# nrf91.net
KiCad netlist of a schematic drawn in Altium Designer
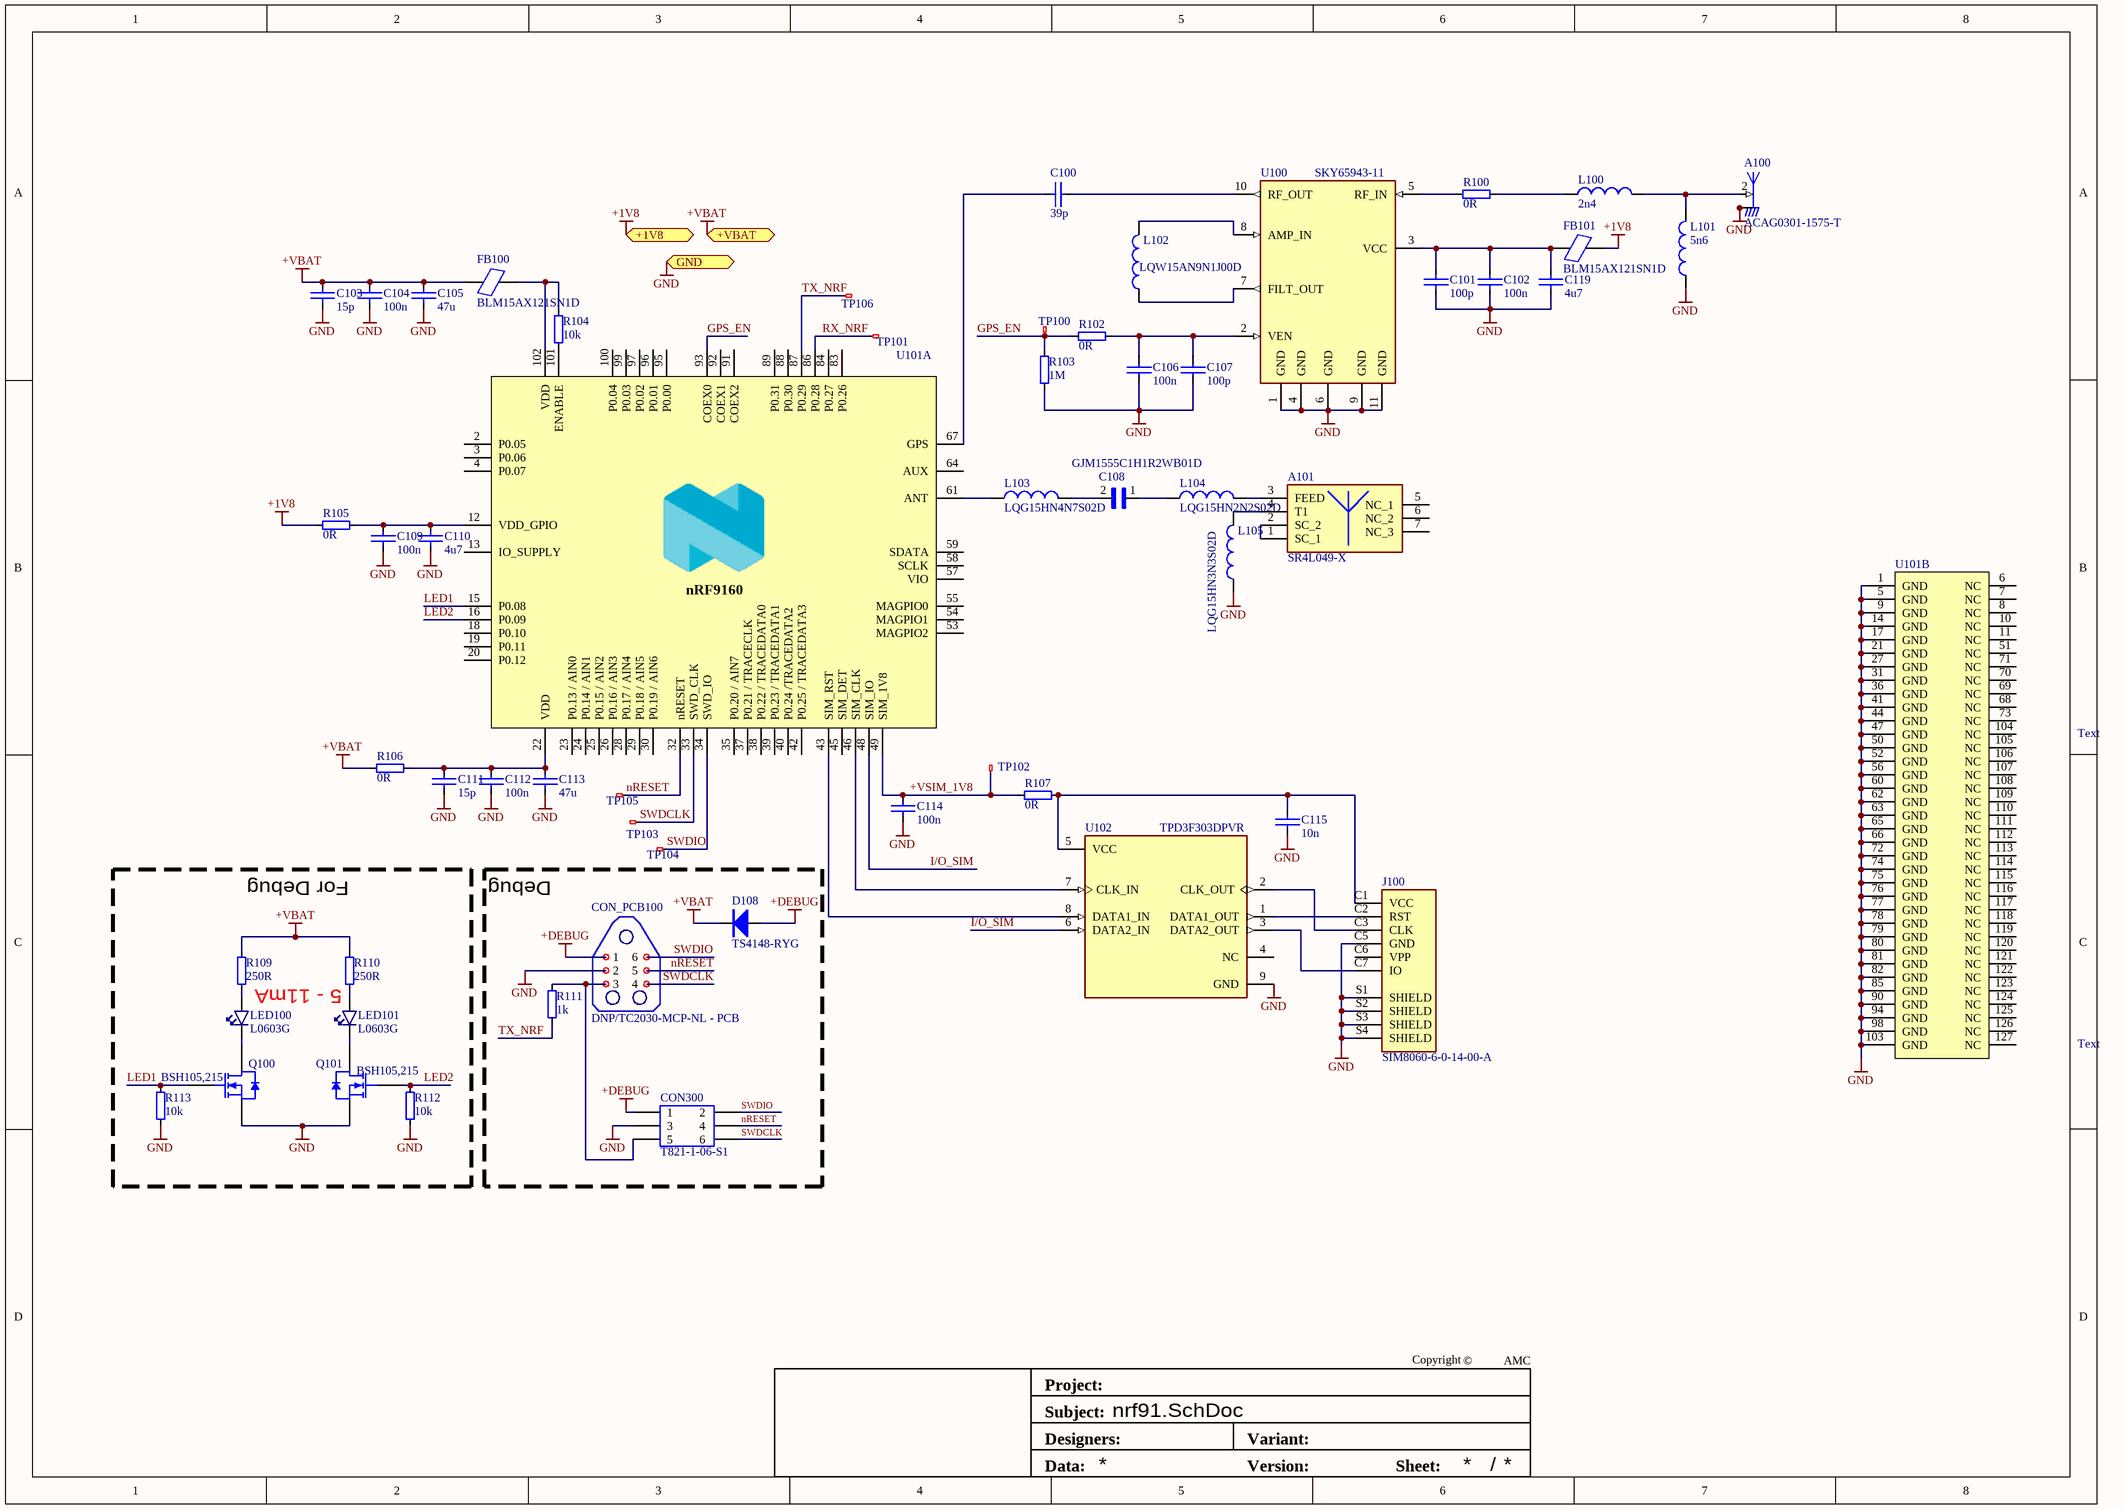
[diagram p0: nrf91.SchDoc]

(export (version "E")
  (design (tool "Eeschema 10.0.6"))
  (components
    (comp (ref "A100")
      (value "ACAG0301-1575-T")
      (footprint "ANT_ACAG0301-1575-T")
      (description "1.575GHz GPS Chip RF Antenna 1.565GHz ~ 1.585GHz 4.18dBi Solder Surface Mount")
      (fields (field (name "MF") "Abracon LLC"))
      (libsource (lib "GPS_LIB_SCH") (part "ACAG0301-1575-T"))
    )
    (comp (ref "A101")
      (value "SR4L049-X")
      (footprint "SR4L049R")
      (description "Antenna")
      (fields (field (name "MANUFACTURER_PART_NUMBER") "SR4L049-R"))
      (libsource (lib "GPS_LIB_SCH") (part "SR4L049-X"))
    )
    (comp (ref "C100")
      (value "39p")
      (footprint "0402_C")
      (description "Capacitor")
      (libsource (lib "ECS_AMC_all_2016") (part "CAP"))
    )
    (comp (ref "C101")
      (value "100p")
      (footprint "0402_C")
      (description "Capacitor")
      (libsource (lib "ECS_AMC_all_2016") (part "CAP"))
    )
    (comp (ref "C102")
      (value "100n")
      (footprint "0402_C")
      (description "Capacitor")
      (libsource (lib "ECS_AMC_all_2016") (part "CAP"))
    )
    (comp (ref "C103")
      (value "15p")
      (footprint "0402_C")
      (description "Capacitor")
      (libsource (lib "ECS_AMC_all_2016") (part "CAP"))
    )
    (comp (ref "C104")
      (value "100n")
      (footprint "0402_C")
      (description "Capacitor")
      (libsource (lib "ECS_AMC_all_2016") (part "CAP"))
    )
    (comp (ref "C105")
      (value "47u")
      (footprint "0805_c")
      (description "Capacitor")
      (libsource (lib "ECS_AMC_all_2016") (part "CAP"))
    )
    (comp (ref "C106")
      (value "100n")
      (footprint "0402_C")
      (description "Capacitor")
      (libsource (lib "ECS_AMC_all_2016") (part "CAP"))
    )
    (comp (ref "C107")
      (value "100p")
      (footprint "0402_C")
      (description "Capacitor")
      (libsource (lib "ECS_AMC_all_2016") (part "CAP"))
    )
    (comp (ref "C108")
      (value "GJM1555C1H1R2WB01D")
      (footprint "CAPC1005X55N")
      (libsource (lib "GPS_LIB_SCH") (part "GJM1555C1H1R2WB01D"))
    )
    (comp (ref "C109")
      (value "100n")
      (footprint "0402_C")
      (description "Capacitor")
      (libsource (lib "ECS_AMC_all_2016") (part "CAP"))
    )
    (comp (ref "C110")
      (value "4u7")
      (footprint "0603_C")
      (description "Capacitor")
      (libsource (lib "ECS_AMC_all_2016") (part "CAP"))
    )
    (comp (ref "C111")
      (value "15p")
      (footprint "0402_C")
      (description "Capacitor")
      (libsource (lib "ECS_AMC_all_2016") (part "CAP"))
    )
    (comp (ref "C112")
      (value "100n")
      (footprint "0402_C")
      (description "Capacitor")
      (libsource (lib "ECS_AMC_all_2016") (part "CAP"))
    )
    (comp (ref "C113")
      (value "47u")
      (footprint "0805_c")
      (description "Capacitor")
      (libsource (lib "ECS_AMC_all_2016") (part "CAP"))
    )
    (comp (ref "C114")
      (value "100n")
      (footprint "0402_C")
      (description "Capacitor")
      (libsource (lib "ECS_AMC_all_2016") (part "CAP"))
    )
    (comp (ref "C115")
      (value "10n")
      (footprint "0402_C")
      (description "Capacitor")
      (libsource (lib "ECS_AMC_all_2016") (part "CAP"))
    )
    (comp (ref "C119")
      (value "4u7")
      (footprint "0603_C")
      (description "Capacitor")
      (libsource (lib "ECS_AMC_all_2016") (part "CAP"))
    )
    (comp (ref "CON300")
      (value "T821-1-06-S1")
      (footprint "IDC_2X3_2.54MM")
      (libsource (lib "ECS_AMC_all_2016") (part "piny_2x3"))
    )
    (comp (ref "CON_PCB100")
      (value "DNP/TC2030-MCP-NL - PCB")
      (footprint "TC2030-MCP-NL - PCB")
      (libsource (lib "ECS_AMC_all_2016") (part "TC2030-MCP-NL - PCB"))
    )
    (comp (ref "D108")
      (value "TS4148-RYG")
      (footprint "0805D")
      (description "Diode")
      (libsource (lib "*") (part "DIODE"))
    )
    (comp (ref "FB100")
      (value "BLM15AX121SN1D")
      (footprint "0402_L")
      (description "Ferrite Bead")
      (libsource (lib "ECS_AMC_all_2016") (part "Ferrite_Bead"))
    )
    (comp (ref "FB101")
      (value "BLM15AX121SN1D")
      (footprint "0402_L")
      (description "Ferrite Bead")
      (libsource (lib "ECS_AMC_all_2016") (part "Ferrite_Bead"))
    )
    (comp (ref "J100")
      (value "SIM8060-6-0-14-00-A")
      (footprint "GCT_SIM8060-6-0-14-00-A")
      (description "6 Position Card Connector NANO SIM Surface Mount, Right Angle Gold")
      (fields (field (name "MF") "Global Connector Technology"))
      (libsource (lib "GPS_LIB_SCH") (part "SIM8060-6-0-14-00-A"))
    )
    (comp (ref "L100")
      (value "2n4")
      (footprint "0402")
      (description "inductor")
      (libsource (lib "ECS_AMC_all_2016") (part "Inductor"))
    )
    (comp (ref "L101")
      (value "5n6")
      (footprint "0402")
      (description "inductor")
      (libsource (lib "ECS_AMC_all_2016") (part "Inductor"))
    )
    (comp (ref "L102")
      (value "LQW15AN9N1J00D")
      (footprint "INDC1006X60N")
      (description "Inductor with Inductance: 9.1nH Tol. +/-5%, Package: 0402 (1005)")
      (fields (field (name "MF") "Murata"))
      (libsource (lib "GPS_LIB_SCH") (part "LQW15AN9N1J00D"))
    )
    (comp (ref "L103")
      (value "LQG15HN4N7S02D")
      (footprint "INDC1005X55N")
      (description "Ind RF Chip Multi-Layer 2.2nH 0.3nH 100MHz 8Q-Factor Air 300mA 0402 Paper T/R")
      (fields (field (name "MP") "LQG15HN2N2S02D"))
      (libsource (lib "GPS_LIB_SCH") (part "LQG15HN4N7S02D"))
    )
    (comp (ref "L104")
      (value "LQG15HN2N2S02D")
      (footprint "INDC1005X55N")
      (description "Ind RF Chip Multi-Layer 2.2nH 0.3nH 100MHz 8Q-Factor Air 300mA 0402 Paper T/R")
      (libsource (lib "GPS_LIB_SCH") (part "LQG15HN2N2S02D"))
    )
    (comp (ref "L105")
      (value "LQG15HN3N3S02D")
      (footprint "INDC1005X55N")
      (description "Ind RF Chip Multi-Layer 2.2nH 0.3nH 100MHz 8Q-Factor Air 300mA 0402 Paper T/R")
      (fields (field (name "MP") "LQG15HN2N2S02D"))
      (libsource (lib "GPS_LIB_SCH") (part "LQG15HN3N3S02D"))
    )
    (comp (ref "LED100")
      (value "L0603G")
      (footprint "LED_0603_G")
      (description "LED, Green, 0603, 573nm, Vf=2.0V, 24mcd, - 40 to +85°C")
      (fields
        (field (name "PART NUMBER") "VS 25C7M5")
        (field (name "MANUFACTURER") "Victory Electronics")
        (field (name "PUBLISHER") "Nordic Semiconductor")
      )
      (libsource (lib "ECS_AMC_all_2016") (part "D{colon}LED"))
    )
    (comp (ref "LED101")
      (value "L0603G")
      (footprint "LED_0603_G")
      (description "LED, Green, 0603, 573nm, Vf=2.0V, 24mcd, - 40 to +85°C")
      (fields
        (field (name "PART NUMBER") "VS 25C7M5")
        (field (name "MANUFACTURER") "Victory Electronics")
        (field (name "PUBLISHER") "Nordic Semiconductor")
      )
      (libsource (lib "ECS_AMC_all_2016") (part "D{colon}LED"))
    )
    (comp (ref "Q100")
      (value "BSH105,215")
      (footprint "SOT23-3D")
      (description "MOSFET N-CH, 170V, 6Ohm, 170mA, Single")
      (libsource (lib "ECS_AMC_all_2016") (part "BSS123_MN"))
    )
    (comp (ref "Q101")
      (value "BSH105,215")
      (footprint "SOT23-3D")
      (description "MOSFET N-CH, 170V, 6Ohm, 170mA, Single")
      (libsource (lib "ECS_AMC_all_2016") (part "BSS123_MN"))
    )
    (comp (ref "R100") (value "0R") (footprint "0402_r") (libsource (lib "ECS_AMC_all_2016") (part "RES")))
    (comp (ref "R102") (value "0R") (footprint "0603") (libsource (lib "ECS_AMC_all_2016") (part "RES")))
    (comp (ref "R103") (value "1M") (footprint "0603") (libsource (lib "") (part "RES_1")))
    (comp (ref "R104") (value "10k") (footprint "0603") (libsource (lib "") (part "RES_1")))
    (comp (ref "R105") (value "0R") (footprint "0603") (libsource (lib "ECS_AMC_all_2016") (part "RES")))
    (comp (ref "R106") (value "0R") (footprint "0603") (libsource (lib "ECS_AMC_all_2016") (part "RES")))
    (comp (ref "R107") (value "0R") (footprint "0603") (libsource (lib "") (part "RES_2")))
    (comp (ref "R109") (value "250R") (footprint "0603") (libsource (lib "ECS_AMC_all_2016") (part "RES")))
    (comp (ref "R110") (value "250R") (footprint "0603") (libsource (lib "ECS_AMC_all_2016") (part "RES")))
    (comp (ref "R111") (value "1k") (footprint "0603") (libsource (lib "") (part "RES_1")))
    (comp (ref "R112") (value "10k") (footprint "0603") (libsource (lib "ECS_AMC_all_2016") (part "RES")))
    (comp (ref "R113") (value "10k") (footprint "0603") (libsource (lib "ECS_AMC_all_2016") (part "RES")))
    (comp (ref "TP100")
      (value "testpointMini")
      (footprint "testpoint_50mils_round")
      (libsource (lib "ECS_AMC_all_2016") (part "testpointMini"))
    )
    (comp (ref "TP101")
      (value "testpointMini")
      (footprint "testpoint_50mils_round")
      (libsource (lib "ECS_AMC_all_2016") (part "testpointMini"))
    )
    (comp (ref "TP102")
      (value "testpointMini")
      (footprint "testpoint_50mils_round")
      (libsource (lib "ECS_AMC_all_2016") (part "testpointMini"))
    )
    (comp (ref "TP103")
      (value "testpointMini")
      (footprint "testpoint_50mils_round")
      (libsource (lib "ECS_AMC_all_2016") (part "testpointMini"))
    )
    (comp (ref "TP104")
      (value "testpointMini")
      (footprint "testpoint_50mils_round")
      (libsource (lib "ECS_AMC_all_2016") (part "testpointMini"))
    )
    (comp (ref "TP105")
      (value "testpointMini")
      (footprint "testpoint_50mils_round")
      (libsource (lib "ECS_AMC_all_2016") (part "testpointMini"))
    )
    (comp (ref "TP106")
      (value "testpointMini")
      (footprint "testpoint_50mils_round")
      (libsource (lib "ECS_AMC_all_2016") (part "testpointMini"))
    )
    (comp (ref "U100")
      (value "SKY65943-11")
      (footprint "IC_SKY65943-11")
      (description "RF Front End 1.559GHz ~ 1.606GHz Galileo, GLONASS, GNSS, GPS 10-MCM (2.5x2.5)")
      (fields (field (name "MF") "Skyworks Solutions Inc."))
      (libsource (lib "GPS_LIB_SCH") (part "SKY65943-11"))
    )
    (comp (ref "U101")
      (value "~")
      (footprint "nRF9160_SIP")
      (libsource (lib "GPS_LIB_SCH") (part "nRF9160_SIP"))
    )
    (comp (ref "U102")
      (value "TPD3F303DPVR")
      (footprint "SON50P210X160X65-9N")
      (libsource (lib "GPS_LIB_SCH") (part "TPD3F303DPVR"))
    )
  )
  (nets
    (net (code "1") (name "+1V8") (class "Default")
      (node (ref "FB101") (pin "2") (pinfunction "2_2") (pintype "passive"))
      (node (ref "R105") (pin "2") (pinfunction "2_2") (pintype "passive"))
    )
    (net (code "2") (name "+DEBUG") (class "Default")
      (node (ref "CON300") (pin "1") (pinfunction "1_1") (pintype "passive"))
      (node (ref "CON_PCB100") (pin "1") (pinfunction "1_1") (pintype "passive"))
      (node (ref "D108") (pin "2") (pinfunction "2_2") (pintype "passive"))
    )
    (net (code "3") (name "+VBAT") (class "Default")
      (node (ref "C103") (pin "2") (pinfunction "2_2") (pintype "passive"))
      (node (ref "C104") (pin "2") (pinfunction "2_2") (pintype "passive"))
      (node (ref "C105") (pin "2") (pinfunction "2_2") (pintype "passive"))
      (node (ref "D108") (pin "1") (pinfunction "1_1") (pintype "passive"))
      (node (ref "FB100") (pin "1") (pinfunction "1_1") (pintype "passive"))
      (node (ref "R106") (pin "2") (pinfunction "2_2") (pintype "passive"))
      (node (ref "R109") (pin "1") (pinfunction "1_1") (pintype "passive"))
      (node (ref "R110") (pin "1") (pinfunction "1_1") (pintype "passive"))
    )
    (net (code "4") (name "/+VSIM_1V8") (class "Default")
      (node (ref "C114") (pin "1") (pinfunction "1_1") (pintype "passive"))
      (node (ref "R107") (pin "1") (pinfunction "1_1") (pintype "passive"))
      (node (ref "TP102") (pin "1") (pinfunction "1_1") (pintype "passive"))
      (node (ref "U101") (pin "49") (pinfunction "SIM_1V8_49") (pintype "passive"))
    )
    (net (code "5") (name "/GPS_EN") (class "Default")
      (node (ref "R102") (pin "2") (pinfunction "2_2") (pintype "passive"))
      (node (ref "R103") (pin "2") (pinfunction "2_2") (pintype "passive"))
      (node (ref "TP100") (pin "1") (pinfunction "1_1") (pintype "passive"))
      (node (ref "U101") (pin "93") (pinfunction "COEX0_93") (pintype "passive"))
    )
    (net (code "6") (name "/I{slash}O_SIM") (class "Default")
      (node (ref "U101") (pin "48") (pinfunction "SIM_IO_48") (pintype "passive"))
      (node (ref "U102") (pin "6") (pinfunction "DATA2_IN_6") (pintype "input"))
    )
    (net (code "7") (name "/LED1") (class "Default")
      (node (ref "Q100") (pin "1") (pinfunction "G_1") (pintype "passive"))
      (node (ref "R113") (pin "1") (pinfunction "1_1") (pintype "passive"))
      (node (ref "U101") (pin "15") (pinfunction "P0.08_15") (pintype "passive"))
    )
    (net (code "8") (name "/LED2") (class "Default")
      (node (ref "Q101") (pin "1") (pinfunction "G_1") (pintype "passive"))
      (node (ref "R112") (pin "1") (pinfunction "1_1") (pintype "passive"))
      (node (ref "U101") (pin "16") (pinfunction "P0.09_16") (pintype "passive"))
    )
    (net (code "9") (name "/RX_NRF") (class "Default")
      (node (ref "TP101") (pin "1") (pinfunction "1_1") (pintype "passive"))
      (node (ref "U101") (pin "86") (pinfunction "P0.28_86") (pintype "passive"))
    )
    (net (code "10") (name "/SWDCLK") (class "Default")
      (node (ref "CON300") (pin "6") (pinfunction "6_6") (pintype "passive"))
      (node (ref "CON_PCB100") (pin "4") (pinfunction "4_4") (pintype "passive"))
      (node (ref "TP103") (pin "1") (pinfunction "1_1") (pintype "passive"))
      (node (ref "U101") (pin "33") (pinfunction "SWD_CLK_33") (pintype "passive"))
    )
    (net (code "11") (name "/SWDIO") (class "Default")
      (node (ref "CON300") (pin "2") (pinfunction "2_2") (pintype "passive"))
      (node (ref "CON_PCB100") (pin "6") (pinfunction "6_6") (pintype "passive"))
      (node (ref "TP104") (pin "1") (pinfunction "1_1") (pintype "passive"))
      (node (ref "U101") (pin "34") (pinfunction "SWD_IO_34") (pintype "passive"))
    )
    (net (code "12") (name "/TX_NRF") (class "Default")
      (node (ref "R111") (pin "1") (pinfunction "1_1") (pintype "passive"))
      (node (ref "TP106") (pin "1") (pinfunction "1_1") (pintype "passive"))
      (node (ref "U101") (pin "87") (pinfunction "P0.29_87") (pintype "passive"))
    )
    (net (code "13") (name "/nRESET") (class "Default")
      (node (ref "CON300") (pin "4") (pinfunction "4_4") (pintype "passive"))
      (node (ref "CON_PCB100") (pin "5") (pinfunction "5_5") (pintype "passive"))
      (node (ref "TP105") (pin "1") (pinfunction "1_1") (pintype "passive"))
      (node (ref "U101") (pin "32") (pinfunction "nRESET_32") (pintype "passive"))
    )
    (net (code "14") (name "GND") (class "Default")
      (node (ref "A100") (pin "1") (pinfunction "2_1") (pintype "passive"))
      (node (ref "A100") (pin "3") (pinfunction "2_3") (pintype "passive"))
      (node (ref "C101") (pin "1") (pinfunction "1_1") (pintype "passive"))
      (node (ref "C102") (pin "1") (pinfunction "1_1") (pintype "passive"))
      (node (ref "C103") (pin "1") (pinfunction "1_1") (pintype "passive"))
      (node (ref "C104") (pin "1") (pinfunction "1_1") (pintype "passive"))
      (node (ref "C105") (pin "1") (pinfunction "1_1") (pintype "passive"))
      (node (ref "C106") (pin "1") (pinfunction "1_1") (pintype "passive"))
      (node (ref "C107") (pin "1") (pinfunction "1_1") (pintype "passive"))
      (node (ref "C109") (pin "1") (pinfunction "1_1") (pintype "passive"))
      (node (ref "C110") (pin "1") (pinfunction "1_1") (pintype "passive"))
      (node (ref "C111") (pin "1") (pinfunction "1_1") (pintype "passive"))
      (node (ref "C112") (pin "1") (pinfunction "1_1") (pintype "passive"))
      (node (ref "C113") (pin "1") (pinfunction "1_1") (pintype "passive"))
      (node (ref "C114") (pin "2") (pinfunction "2_2") (pintype "passive"))
      (node (ref "C115") (pin "1") (pinfunction "1_1") (pintype "passive"))
      (node (ref "C119") (pin "1") (pinfunction "1_1") (pintype "passive"))
      (node (ref "CON300") (pin "3") (pinfunction "3_3") (pintype "passive"))
      (node (ref "CON_PCB100") (pin "2") (pinfunction "2_2") (pintype "passive"))
      (node (ref "J100") (pin "C5") (pinfunction "GND_C5") (pintype "passive"))
      (node (ref "J100") (pin "S1") (pinfunction "SHIELD_S1") (pintype "passive"))
      (node (ref "J100") (pin "S2") (pinfunction "SHIELD_S2") (pintype "passive"))
      (node (ref "J100") (pin "S3") (pinfunction "SHIELD_S3") (pintype "passive"))
      (node (ref "J100") (pin "S4") (pinfunction "SHIELD_S4") (pintype "passive"))
      (node (ref "L101") (pin "1") (pinfunction "1_1") (pintype "passive"))
      (node (ref "L105") (pin "1") (pinfunction "1_1") (pintype "passive"))
      (node (ref "Q100") (pin "2") (pinfunction "S_2") (pintype "passive"))
      (node (ref "Q101") (pin "2") (pinfunction "S_2") (pintype "passive"))
      (node (ref "R103") (pin "1") (pinfunction "1_1") (pintype "passive"))
      (node (ref "R112") (pin "2") (pinfunction "2_2") (pintype "passive"))
      (node (ref "R113") (pin "2") (pinfunction "2_2") (pintype "passive"))
      (node (ref "U100") (pin "1") (pinfunction "GND_1") (pintype "passive"))
      (node (ref "U100") (pin "11") (pinfunction "GND_11") (pintype "passive"))
      (node (ref "U100") (pin "4") (pinfunction "GND_4") (pintype "passive"))
      (node (ref "U100") (pin "6") (pinfunction "GND_6") (pintype "passive"))
      (node (ref "U100") (pin "9") (pinfunction "GND_9") (pintype "passive"))
      (node (ref "U101") (pin "1") (pinfunction "GND_1") (pintype "passive"))
      (node (ref "U101") (pin "103") (pinfunction "GND_103") (pintype "passive"))
      (node (ref "U101") (pin "14") (pinfunction "GND_14") (pintype "passive"))
      (node (ref "U101") (pin "17") (pinfunction "GND_17") (pintype "passive"))
      (node (ref "U101") (pin "21") (pinfunction "GND_21") (pintype "passive"))
      (node (ref "U101") (pin "27") (pinfunction "GND_27") (pintype "passive"))
      (node (ref "U101") (pin "31") (pinfunction "GND_31") (pintype "passive"))
      (node (ref "U101") (pin "36") (pinfunction "GND_36") (pintype "passive"))
      (node (ref "U101") (pin "41") (pinfunction "GND_41") (pintype "passive"))
      (node (ref "U101") (pin "44") (pinfunction "GND_44") (pintype "passive"))
      (node (ref "U101") (pin "47") (pinfunction "GND_47") (pintype "passive"))
      (node (ref "U101") (pin "5") (pinfunction "GND_5") (pintype "passive"))
      (node (ref "U101") (pin "50") (pinfunction "GND_50") (pintype "passive"))
      (node (ref "U101") (pin "52") (pinfunction "GND_52") (pintype "passive"))
      (node (ref "U101") (pin "56") (pinfunction "GND_56") (pintype "passive"))
      (node (ref "U101") (pin "60") (pinfunction "GND_60") (pintype "passive"))
      (node (ref "U101") (pin "62") (pinfunction "GND_62") (pintype "passive"))
      (node (ref "U101") (pin "63") (pinfunction "GND_63") (pintype "passive"))
      (node (ref "U101") (pin "65") (pinfunction "GND_65") (pintype "passive"))
      (node (ref "U101") (pin "66") (pinfunction "GND_66") (pintype "passive"))
      (node (ref "U101") (pin "72") (pinfunction "GND_72") (pintype "passive"))
      (node (ref "U101") (pin "74") (pinfunction "GND_74") (pintype "passive"))
      (node (ref "U101") (pin "75") (pinfunction "GND_75") (pintype "passive"))
      (node (ref "U101") (pin "76") (pinfunction "GND_76") (pintype "passive"))
      (node (ref "U101") (pin "77") (pinfunction "GND_77") (pintype "passive"))
      (node (ref "U101") (pin "78") (pinfunction "GND_78") (pintype "passive"))
      (node (ref "U101") (pin "79") (pinfunction "GND_79") (pintype "passive"))
      (node (ref "U101") (pin "80") (pinfunction "GND_80") (pintype "passive"))
      (node (ref "U101") (pin "81") (pinfunction "GND_81") (pintype "passive"))
      (node (ref "U101") (pin "82") (pinfunction "GND_82") (pintype "passive"))
      (node (ref "U101") (pin "85") (pinfunction "GND_85") (pintype "passive"))
      (node (ref "U101") (pin "9") (pinfunction "GND_9") (pintype "passive"))
      (node (ref "U101") (pin "90") (pinfunction "GND_90") (pintype "passive"))
      (node (ref "U101") (pin "94") (pinfunction "GND_94") (pintype "passive"))
      (node (ref "U101") (pin "98") (pinfunction "GND_98") (pintype "passive"))
      (node (ref "U102") (pin "9") (pinfunction "GND_9") (pintype "passive"))
    )
    (net (code "15") (name "Net-(A100-1)") (class "Default")
      (node (ref "A100") (pin "2") (pinfunction "1_2") (pintype "input"))
      (node (ref "L100") (pin "2") (pinfunction "2_2") (pintype "passive"))
      (node (ref "L101") (pin "2") (pinfunction "2_2") (pintype "passive"))
    )
    (net (code "16") (name "Net-(A101-FEED)") (class "Default")
      (node (ref "A101") (pin "3") (pinfunction "FEED_3") (pintype "passive"))
      (node (ref "L104") (pin "2") (pinfunction "2_2") (pintype "passive"))
    )
    (net (code "17") (name "Net-(A101-SC_1)") (class "Default")
      (node (ref "A101") (pin "1") (pinfunction "SC_1_1") (pintype "passive"))
      (node (ref "A101") (pin "2") (pinfunction "SC_2_2") (pintype "passive"))
    )
    (net (code "18") (name "Net-(A101-T1)") (class "Default")
      (node (ref "A101") (pin "4") (pinfunction "T1_4") (pintype "passive"))
      (node (ref "L105") (pin "2") (pinfunction "2_2") (pintype "passive"))
    )
    (net (code "19") (name "Net-(C108-Pad1)") (class "Default")
      (node (ref "C108") (pin "1") (pinfunction "1_1") (pintype "passive"))
      (node (ref "L104") (pin "1") (pinfunction "1_1") (pintype "passive"))
    )
    (net (code "20") (name "Net-(C108-Pad2)") (class "Default")
      (node (ref "C108") (pin "2") (pinfunction "2_2") (pintype "passive"))
      (node (ref "L103") (pin "2") (pinfunction "2_2") (pintype "passive"))
    )
    (net (code "21") (name "Net-(C111-Pad2)") (class "Default")
      (node (ref "C111") (pin "2") (pinfunction "2_2") (pintype "passive"))
      (node (ref "C112") (pin "2") (pinfunction "2_2") (pintype "passive"))
      (node (ref "C113") (pin "2") (pinfunction "2_2") (pintype "passive"))
      (node (ref "R106") (pin "1") (pinfunction "1_1") (pintype "passive"))
      (node (ref "U101") (pin "22") (pinfunction "VDD_22") (pintype "passive"))
    )
    (net (code "22") (name "Net-(CON300-Pad5)") (class "Default")
      (node (ref "CON300") (pin "5") (pinfunction "5_5") (pintype "passive"))
      (node (ref "CON_PCB100") (pin "3") (pinfunction "3_3") (pintype "passive"))
      (node (ref "R111") (pin "2") (pinfunction "2_2") (pintype "passive"))
    )
    (net (code "23") (name "Net-(FB100-Pad2)") (class "Default")
      (node (ref "FB100") (pin "2") (pinfunction "2_2") (pintype "passive"))
      (node (ref "R104") (pin "2") (pinfunction "2_2") (pintype "passive"))
      (node (ref "U101") (pin "102") (pinfunction "VDD_102") (pintype "passive"))
    )
    (net (code "24") (name "Net-(J100-CLK)") (class "Default")
      (node (ref "J100") (pin "C3") (pinfunction "CLK_C3") (pintype "passive"))
      (node (ref "U102") (pin "2") (pinfunction "CLK_OUT_2") (pintype "output"))
    )
    (net (code "25") (name "Net-(J100-IO)") (class "Default")
      (node (ref "J100") (pin "C7") (pinfunction "IO_C7") (pintype "passive"))
      (node (ref "U102") (pin "3") (pinfunction "DATA2_OUT_3") (pintype "output"))
    )
    (net (code "26") (name "Net-(J100-RST)") (class "Default")
      (node (ref "J100") (pin "C2") (pinfunction "RST_C2") (pintype "passive"))
      (node (ref "U102") (pin "1") (pinfunction "DATA1_OUT_1") (pintype "output"))
    )
    (net (code "27") (name "Net-(J100-VCC)") (class "Default")
      (node (ref "C115") (pin "2") (pinfunction "2_2") (pintype "passive"))
      (node (ref "J100") (pin "C1") (pinfunction "VCC_C1") (pintype "passive"))
      (node (ref "R107") (pin "2") (pinfunction "2_2") (pintype "passive"))
      (node (ref "U102") (pin "5") (pinfunction "VCC_5") (pintype "passive"))
    )
    (net (code "28") (name "Net-(L100-Pad1)") (class "Default")
      (node (ref "L100") (pin "1") (pinfunction "1_1") (pintype "passive"))
      (node (ref "R100") (pin "1") (pinfunction "1_1") (pintype "passive"))
    )
    (net (code "29") (name "Net-(LED100-A)") (class "Default")
      (node (ref "LED100") (pin "2") (pinfunction "A_2") (pintype "passive"))
      (node (ref "R109") (pin "2") (pinfunction "2_2") (pintype "passive"))
    )
    (net (code "30") (name "Net-(LED100-C)") (class "Default")
      (node (ref "LED100") (pin "1") (pinfunction "C_1") (pintype "passive"))
      (node (ref "Q100") (pin "3") (pinfunction "D_3") (pintype "passive"))
    )
    (net (code "31") (name "Net-(LED101-A)") (class "Default")
      (node (ref "LED101") (pin "2") (pinfunction "A_2") (pintype "passive"))
      (node (ref "R110") (pin "2") (pinfunction "2_2") (pintype "passive"))
    )
    (net (code "32") (name "Net-(LED101-C)") (class "Default")
      (node (ref "LED101") (pin "1") (pinfunction "C_1") (pintype "passive"))
      (node (ref "Q101") (pin "3") (pinfunction "D_3") (pintype "passive"))
    )
    (net (code "33") (name "Net-(U100-AMP_IN)") (class "Default")
      (node (ref "L102") (pin "2") (pinfunction "2_2") (pintype "passive"))
      (node (ref "U100") (pin "8") (pinfunction "AMP_IN_8") (pintype "input"))
    )
    (net (code "34") (name "Net-(U100-FILT_OUT)") (class "Default")
      (node (ref "L102") (pin "1") (pinfunction "1_1") (pintype "passive"))
      (node (ref "U100") (pin "7") (pinfunction "FILT_OUT_7") (pintype "output"))
    )
    (net (code "35") (name "Net-(U100-RF_IN)") (class "Default")
      (node (ref "R100") (pin "2") (pinfunction "2_2") (pintype "passive"))
      (node (ref "U100") (pin "5") (pinfunction "RF_IN_5") (pintype "input"))
    )
    (net (code "36") (name "Net-(U100-RF_OUT)") (class "Default")
      (node (ref "C100") (pin "1") (pinfunction "1_1") (pintype "passive"))
      (node (ref "U100") (pin "10") (pinfunction "RF_OUT_10") (pintype "output"))
    )
    (net (code "37") (name "Net-(U100-VCC)") (class "Default")
      (node (ref "C101") (pin "2") (pinfunction "2_2") (pintype "passive"))
      (node (ref "C102") (pin "2") (pinfunction "2_2") (pintype "passive"))
      (node (ref "C119") (pin "2") (pinfunction "2_2") (pintype "passive"))
      (node (ref "FB101") (pin "1") (pinfunction "1_1") (pintype "passive"))
      (node (ref "U100") (pin "3") (pinfunction "VCC_3") (pintype "passive"))
    )
    (net (code "38") (name "Net-(U100-VEN)") (class "Default")
      (node (ref "C106") (pin "2") (pinfunction "2_2") (pintype "passive"))
      (node (ref "C107") (pin "2") (pinfunction "2_2") (pintype "passive"))
      (node (ref "R102") (pin "1") (pinfunction "1_1") (pintype "passive"))
      (node (ref "U100") (pin "2") (pinfunction "VEN_2") (pintype "input"))
    )
    (net (code "39") (name "Net-(U101A-ANT)") (class "Default")
      (node (ref "L103") (pin "1") (pinfunction "1_1") (pintype "passive"))
      (node (ref "U101") (pin "61") (pinfunction "ANT_61") (pintype "passive"))
    )
    (net (code "40") (name "Net-(U101A-ENABLE)") (class "Default")
      (node (ref "R104") (pin "1") (pinfunction "1_1") (pintype "passive"))
      (node (ref "U101") (pin "101") (pinfunction "ENABLE_101") (pintype "passive"))
    )
    (net (code "41") (name "Net-(U101A-GPS)") (class "Default")
      (node (ref "C100") (pin "2") (pinfunction "2_2") (pintype "passive"))
      (node (ref "U101") (pin "67") (pinfunction "GPS_67") (pintype "passive"))
    )
    (net (code "42") (name "Net-(U101A-SIM_CLK)") (class "Default")
      (node (ref "U101") (pin "46") (pinfunction "SIM_CLK_46") (pintype "passive"))
      (node (ref "U102") (pin "7") (pinfunction "CLK_IN_7") (pintype "input"))
    )
    (net (code "43") (name "Net-(U101A-SIM_RST)") (class "Default")
      (node (ref "U101") (pin "43") (pinfunction "SIM_RST_43") (pintype "passive"))
      (node (ref "U102") (pin "8") (pinfunction "DATA1_IN_8") (pintype "input"))
    )
    (net (code "44") (name "Net-(U101A-VDD_GPIO)") (class "Default")
      (node (ref "C109") (pin "2") (pinfunction "2_2") (pintype "passive"))
      (node (ref "C110") (pin "2") (pinfunction "2_2") (pintype "passive"))
      (node (ref "R105") (pin "1") (pinfunction "1_1") (pintype "passive"))
      (node (ref "U101") (pin "12") (pinfunction "VDD_GPIO_12") (pintype "passive"))
    )
    (net (code "45") (name "unconnected-(A101-NC_1-Pad5)") (class "Default")
      (node (ref "A101") (pin "5") (pinfunction "NC_1_5") (pintype "passive"))
    )
    (net (code "46") (name "unconnected-(A101-NC_2-Pad6)") (class "Default")
      (node (ref "A101") (pin "6") (pinfunction "NC_2_6") (pintype "passive"))
    )
    (net (code "47") (name "unconnected-(A101-NC_3-Pad7)") (class "Default")
      (node (ref "A101") (pin "7") (pinfunction "NC_3_7") (pintype "passive"))
    )
    (net (code "48") (name "unconnected-(J100-VPP-PadC6)") (class "Default")
      (node (ref "J100") (pin "C6") (pinfunction "VPP_C6") (pintype "passive"))
    )
    (net (code "49") (name "unconnected-(U101A-AUX-Pad64)") (class "Default")
      (node (ref "U101") (pin "64") (pinfunction "AUX_64") (pintype "passive"))
    )
    (net (code "50") (name "unconnected-(U101A-COEX1-Pad92)") (class "Default")
      (node (ref "U101") (pin "92") (pinfunction "COEX1_92") (pintype "passive"))
    )
    (net (code "51") (name "unconnected-(U101A-COEX2-Pad91)") (class "Default")
      (node (ref "U101") (pin "91") (pinfunction "COEX2_91") (pintype "passive"))
    )
    (net (code "52") (name "unconnected-(U101A-GND-Pad1)") (class "Default")
      (node (ref "U101") (pin "1") (pinfunction "GND_1") (pintype "passive"))
    )
    (net (code "53") (name "unconnected-(U101A-GND-Pad5)") (class "Default")
      (node (ref "U101") (pin "5") (pinfunction "GND_5") (pintype "passive"))
    )
    (net (code "54") (name "unconnected-(U101A-GND-Pad9)") (class "Default")
      (node (ref "U101") (pin "9") (pinfunction "GND_9") (pintype "passive"))
    )
    (net (code "55") (name "unconnected-(U101A-GND-Pad14)") (class "Default")
      (node (ref "U101") (pin "14") (pinfunction "GND_14") (pintype "passive"))
    )
    (net (code "56") (name "unconnected-(U101A-GND-Pad17)") (class "Default")
      (node (ref "U101") (pin "17") (pinfunction "GND_17") (pintype "passive"))
    )
    (net (code "57") (name "unconnected-(U101A-GND-Pad21)") (class "Default")
      (node (ref "U101") (pin "21") (pinfunction "GND_21") (pintype "passive"))
    )
    (net (code "58") (name "unconnected-(U101A-GND-Pad27)") (class "Default")
      (node (ref "U101") (pin "27") (pinfunction "GND_27") (pintype "passive"))
    )
    (net (code "59") (name "unconnected-(U101A-GND-Pad31)") (class "Default")
      (node (ref "U101") (pin "31") (pinfunction "GND_31") (pintype "passive"))
    )
    (net (code "60") (name "unconnected-(U101A-GND-Pad36)") (class "Default")
      (node (ref "U101") (pin "36") (pinfunction "GND_36") (pintype "passive"))
    )
    (net (code "61") (name "unconnected-(U101A-GND-Pad41)") (class "Default")
      (node (ref "U101") (pin "41") (pinfunction "GND_41") (pintype "passive"))
    )
    (net (code "62") (name "unconnected-(U101A-GND-Pad44)") (class "Default")
      (node (ref "U101") (pin "44") (pinfunction "GND_44") (pintype "passive"))
    )
    (net (code "63") (name "unconnected-(U101A-GND-Pad47)") (class "Default")
      (node (ref "U101") (pin "47") (pinfunction "GND_47") (pintype "passive"))
    )
    (net (code "64") (name "unconnected-(U101A-GND-Pad50)") (class "Default")
      (node (ref "U101") (pin "50") (pinfunction "GND_50") (pintype "passive"))
    )
    (net (code "65") (name "unconnected-(U101A-GND-Pad52)") (class "Default")
      (node (ref "U101") (pin "52") (pinfunction "GND_52") (pintype "passive"))
    )
    (net (code "66") (name "unconnected-(U101A-GND-Pad56)") (class "Default")
      (node (ref "U101") (pin "56") (pinfunction "GND_56") (pintype "passive"))
    )
    (net (code "67") (name "unconnected-(U101A-GND-Pad60)") (class "Default")
      (node (ref "U101") (pin "60") (pinfunction "GND_60") (pintype "passive"))
    )
    (net (code "68") (name "unconnected-(U101A-GND-Pad62)") (class "Default")
      (node (ref "U101") (pin "62") (pinfunction "GND_62") (pintype "passive"))
    )
    (net (code "69") (name "unconnected-(U101A-GND-Pad63)") (class "Default")
      (node (ref "U101") (pin "63") (pinfunction "GND_63") (pintype "passive"))
    )
    (net (code "70") (name "unconnected-(U101A-GND-Pad65)") (class "Default")
      (node (ref "U101") (pin "65") (pinfunction "GND_65") (pintype "passive"))
    )
    (net (code "71") (name "unconnected-(U101A-GND-Pad66)") (class "Default")
      (node (ref "U101") (pin "66") (pinfunction "GND_66") (pintype "passive"))
    )
    (net (code "72") (name "unconnected-(U101A-GND-Pad72)") (class "Default")
      (node (ref "U101") (pin "72") (pinfunction "GND_72") (pintype "passive"))
    )
    (net (code "73") (name "unconnected-(U101A-GND-Pad74)") (class "Default")
      (node (ref "U101") (pin "74") (pinfunction "GND_74") (pintype "passive"))
    )
    (net (code "74") (name "unconnected-(U101A-GND-Pad75)") (class "Default")
      (node (ref "U101") (pin "75") (pinfunction "GND_75") (pintype "passive"))
    )
    (net (code "75") (name "unconnected-(U101A-GND-Pad76)") (class "Default")
      (node (ref "U101") (pin "76") (pinfunction "GND_76") (pintype "passive"))
    )
    (net (code "76") (name "unconnected-(U101A-GND-Pad77)") (class "Default")
      (node (ref "U101") (pin "77") (pinfunction "GND_77") (pintype "passive"))
    )
    (net (code "77") (name "unconnected-(U101A-GND-Pad78)") (class "Default")
      (node (ref "U101") (pin "78") (pinfunction "GND_78") (pintype "passive"))
    )
    (net (code "78") (name "unconnected-(U101A-GND-Pad79)") (class "Default")
      (node (ref "U101") (pin "79") (pinfunction "GND_79") (pintype "passive"))
    )
    (net (code "79") (name "unconnected-(U101A-GND-Pad80)") (class "Default")
      (node (ref "U101") (pin "80") (pinfunction "GND_80") (pintype "passive"))
    )
    (net (code "80") (name "unconnected-(U101A-GND-Pad81)") (class "Default")
      (node (ref "U101") (pin "81") (pinfunction "GND_81") (pintype "passive"))
    )
    (net (code "81") (name "unconnected-(U101A-GND-Pad82)") (class "Default")
      (node (ref "U101") (pin "82") (pinfunction "GND_82") (pintype "passive"))
    )
    (net (code "82") (name "unconnected-(U101A-GND-Pad85)") (class "Default")
      (node (ref "U101") (pin "85") (pinfunction "GND_85") (pintype "passive"))
    )
    (net (code "83") (name "unconnected-(U101A-GND-Pad90)") (class "Default")
      (node (ref "U101") (pin "90") (pinfunction "GND_90") (pintype "passive"))
    )
    (net (code "84") (name "unconnected-(U101A-GND-Pad94)") (class "Default")
      (node (ref "U101") (pin "94") (pinfunction "GND_94") (pintype "passive"))
    )
    (net (code "85") (name "unconnected-(U101A-GND-Pad98)") (class "Default")
      (node (ref "U101") (pin "98") (pinfunction "GND_98") (pintype "passive"))
    )
    (net (code "86") (name "unconnected-(U101A-GND-Pad103)") (class "Default")
      (node (ref "U101") (pin "103") (pinfunction "GND_103") (pintype "passive"))
    )
    (net (code "87") (name "unconnected-(U101A-IO_SUPPLY-Pad13)") (class "Default")
      (node (ref "U101") (pin "13") (pinfunction "IO_SUPPLY_13") (pintype "passive"))
    )
    (net (code "88") (name "unconnected-(U101A-MAGPIO0-Pad55)") (class "Default")
      (node (ref "U101") (pin "55") (pinfunction "MAGPIO0_55") (pintype "passive"))
    )
    (net (code "89") (name "unconnected-(U101A-MAGPIO1-Pad54)") (class "Default")
      (node (ref "U101") (pin "54") (pinfunction "MAGPIO1_54") (pintype "passive"))
    )
    (net (code "90") (name "unconnected-(U101A-MAGPIO2-Pad53)") (class "Default")
      (node (ref "U101") (pin "53") (pinfunction "MAGPIO2_53") (pintype "passive"))
    )
    (net (code "91") (name "unconnected-(U101A-P0.00-Pad95)") (class "Default")
      (node (ref "U101") (pin "95") (pinfunction "P0.00_95") (pintype "passive"))
    )
    (net (code "92") (name "unconnected-(U101A-P0.01-Pad96)") (class "Default")
      (node (ref "U101") (pin "96") (pinfunction "P0.01_96") (pintype "passive"))
    )
    (net (code "93") (name "unconnected-(U101A-P0.02-Pad97)") (class "Default")
      (node (ref "U101") (pin "97") (pinfunction "P0.02_97") (pintype "passive"))
    )
    (net (code "94") (name "unconnected-(U101A-P0.03-Pad99)") (class "Default")
      (node (ref "U101") (pin "99") (pinfunction "P0.03_99") (pintype "passive"))
    )
    (net (code "95") (name "unconnected-(U101A-P0.04-Pad100)") (class "Default")
      (node (ref "U101") (pin "100") (pinfunction "P0.04_100") (pintype "passive"))
    )
    (net (code "96") (name "unconnected-(U101A-P0.05-Pad2)") (class "Default")
      (node (ref "U101") (pin "2") (pinfunction "P0.05_2") (pintype "passive"))
    )
    (net (code "97") (name "unconnected-(U101A-P0.06-Pad3)") (class "Default")
      (node (ref "U101") (pin "3") (pinfunction "P0.06_3") (pintype "passive"))
    )
    (net (code "98") (name "unconnected-(U101A-P0.07-Pad4)") (class "Default")
      (node (ref "U101") (pin "4") (pinfunction "P0.07_4") (pintype "passive"))
    )
    (net (code "99") (name "unconnected-(U101A-P0.10-Pad18)") (class "Default")
      (node (ref "U101") (pin "18") (pinfunction "P0.10_18") (pintype "passive"))
    )
    (net (code "100") (name "unconnected-(U101A-P0.11-Pad19)") (class "Default")
      (node (ref "U101") (pin "19") (pinfunction "P0.11_19") (pintype "passive"))
    )
    (net (code "101") (name "unconnected-(U101A-P0.12-Pad20)") (class "Default")
      (node (ref "U101") (pin "20") (pinfunction "P0.12_20") (pintype "passive"))
    )
    (net (code "102") (name "unconnected-(U101A-P0.13_{slash}_AIN0-Pad23)") (class "Default")
      (node (ref "U101") (pin "23") (pinfunction "P0.13_/_AIN0_23") (pintype "passive"))
    )
    (net (code "103") (name "unconnected-(U101A-P0.14_{slash}_AIN1-Pad24)") (class "Default")
      (node (ref "U101") (pin "24") (pinfunction "P0.14_/_AIN1_24") (pintype "passive"))
    )
    (net (code "104") (name "unconnected-(U101A-P0.15_{slash}_AIN2-Pad25)") (class "Default")
      (node (ref "U101") (pin "25") (pinfunction "P0.15_/_AIN2_25") (pintype "passive"))
    )
    (net (code "105") (name "unconnected-(U101A-P0.16_{slash}_AIN3-Pad26)") (class "Default")
      (node (ref "U101") (pin "26") (pinfunction "P0.16_/_AIN3_26") (pintype "passive"))
    )
    (net (code "106") (name "unconnected-(U101A-P0.17_{slash}_AIN4-Pad28)") (class "Default")
      (node (ref "U101") (pin "28") (pinfunction "P0.17_/_AIN4_28") (pintype "passive"))
    )
    (net (code "107") (name "unconnected-(U101A-P0.18_{slash}_AIN5-Pad29)") (class "Default")
      (node (ref "U101") (pin "29") (pinfunction "P0.18_/_AIN5_29") (pintype "passive"))
    )
    (net (code "108") (name "unconnected-(U101A-P0.19_{slash}_AIN6-Pad30)") (class "Default")
      (node (ref "U101") (pin "30") (pinfunction "P0.19_/_AIN6_30") (pintype "passive"))
    )
    (net (code "109") (name "unconnected-(U101A-P0.20_{slash}_AIN7-Pad35)") (class "Default")
      (node (ref "U101") (pin "35") (pinfunction "P0.20_/_AIN7_35") (pintype "passive"))
    )
    (net (code "110") (name "unconnected-(U101A-P0.21_{slash}_TRACECLK-Pad37)") (class "Default")
      (node (ref "U101") (pin "37") (pinfunction "P0.21_/_TRACECLK_37") (pintype "passive"))
    )
    (net (code "111") (name "unconnected-(U101A-P0.22_{slash}_TRACEDATA0-Pad38)") (class "Default")
      (node (ref "U101") (pin "38") (pinfunction "P0.22_/_TRACEDATA0_38") (pintype "passive"))
    )
    (net (code "112") (name "unconnected-(U101A-P0.23_{slash}_TRACEDATA1-Pad39)") (class "Default")
      (node (ref "U101") (pin "39") (pinfunction "P0.23_/_TRACEDATA1_39") (pintype "passive"))
    )
    (net (code "113") (name "unconnected-(U101A-P0.24_{slash}TRACEDATA2-Pad40)") (class "Default")
      (node (ref "U101") (pin "40") (pinfunction "P0.24_/TRACEDATA2_40") (pintype "passive"))
    )
    (net (code "114") (name "unconnected-(U101A-P0.25_{slash}_TRACEDATA3-Pad42)") (class "Default")
      (node (ref "U101") (pin "42") (pinfunction "P0.25_/_TRACEDATA3_42") (pintype "passive"))
    )
    (net (code "115") (name "unconnected-(U101A-P0.26-Pad83)") (class "Default")
      (node (ref "U101") (pin "83") (pinfunction "P0.26_83") (pintype "passive"))
    )
    (net (code "116") (name "unconnected-(U101A-P0.27-Pad84)") (class "Default")
      (node (ref "U101") (pin "84") (pinfunction "P0.27_84") (pintype "passive"))
    )
    (net (code "117") (name "unconnected-(U101A-P0.30-Pad88)") (class "Default")
      (node (ref "U101") (pin "88") (pinfunction "P0.30_88") (pintype "passive"))
    )
    (net (code "118") (name "unconnected-(U101A-P0.31-Pad89)") (class "Default")
      (node (ref "U101") (pin "89") (pinfunction "P0.31_89") (pintype "passive"))
    )
    (net (code "119") (name "unconnected-(U101A-SCLK-Pad58)") (class "Default")
      (node (ref "U101") (pin "58") (pinfunction "SCLK_58") (pintype "passive"))
    )
    (net (code "120") (name "unconnected-(U101A-SDATA-Pad59)") (class "Default")
      (node (ref "U101") (pin "59") (pinfunction "SDATA_59") (pintype "passive"))
    )
    (net (code "121") (name "unconnected-(U101A-SIM_DET-Pad45)") (class "Default")
      (node (ref "U101") (pin "45") (pinfunction "SIM_DET_45") (pintype "passive"))
    )
    (net (code "122") (name "unconnected-(U101A-VIO-Pad57)") (class "Default")
      (node (ref "U101") (pin "57") (pinfunction "VIO_57") (pintype "passive"))
    )
    (net (code "123") (name "unconnected-(U101B-NC-Pad6)") (class "Default")
      (node (ref "U101") (pin "6") (pinfunction "NC_6") (pintype "passive"))
    )
    (net (code "124") (name "unconnected-(U101B-NC-Pad7)") (class "Default")
      (node (ref "U101") (pin "7") (pinfunction "NC_7") (pintype "passive"))
    )
    (net (code "125") (name "unconnected-(U101B-NC-Pad8)") (class "Default")
      (node (ref "U101") (pin "8") (pinfunction "NC_8") (pintype "passive"))
    )
    (net (code "126") (name "unconnected-(U101B-NC-Pad10)") (class "Default")
      (node (ref "U101") (pin "10") (pinfunction "NC_10") (pintype "passive"))
    )
    (net (code "127") (name "unconnected-(U101B-NC-Pad11)") (class "Default")
      (node (ref "U101") (pin "11") (pinfunction "NC_11") (pintype "passive"))
    )
    (net (code "128") (name "unconnected-(U101B-NC-Pad51)") (class "Default")
      (node (ref "U101") (pin "51") (pinfunction "NC_51") (pintype "passive"))
    )
    (net (code "129") (name "unconnected-(U101B-NC-Pad68)") (class "Default")
      (node (ref "U101") (pin "68") (pinfunction "NC_68") (pintype "passive"))
    )
    (net (code "130") (name "unconnected-(U101B-NC-Pad69)") (class "Default")
      (node (ref "U101") (pin "69") (pinfunction "NC_69") (pintype "passive"))
    )
    (net (code "131") (name "unconnected-(U101B-NC-Pad70)") (class "Default")
      (node (ref "U101") (pin "70") (pinfunction "NC_70") (pintype "passive"))
    )
    (net (code "132") (name "unconnected-(U101B-NC-Pad71)") (class "Default")
      (node (ref "U101") (pin "71") (pinfunction "NC_71") (pintype "passive"))
    )
    (net (code "133") (name "unconnected-(U101B-NC-Pad73)") (class "Default")
      (node (ref "U101") (pin "73") (pinfunction "NC_73") (pintype "passive"))
    )
    (net (code "134") (name "unconnected-(U101B-NC-Pad104)") (class "Default")
      (node (ref "U101") (pin "104") (pinfunction "NC_104") (pintype "passive"))
    )
    (net (code "135") (name "unconnected-(U101B-NC-Pad105)") (class "Default")
      (node (ref "U101") (pin "105") (pinfunction "NC_105") (pintype "passive"))
    )
    (net (code "136") (name "unconnected-(U101B-NC-Pad106)") (class "Default")
      (node (ref "U101") (pin "106") (pinfunction "NC_106") (pintype "passive"))
    )
    (net (code "137") (name "unconnected-(U101B-NC-Pad107)") (class "Default")
      (node (ref "U101") (pin "107") (pinfunction "NC_107") (pintype "passive"))
    )
    (net (code "138") (name "unconnected-(U101B-NC-Pad108)") (class "Default")
      (node (ref "U101") (pin "108") (pinfunction "NC_108") (pintype "passive"))
    )
    (net (code "139") (name "unconnected-(U101B-NC-Pad109)") (class "Default")
      (node (ref "U101") (pin "109") (pinfunction "NC_109") (pintype "passive"))
    )
    (net (code "140") (name "unconnected-(U101B-NC-Pad110)") (class "Default")
      (node (ref "U101") (pin "110") (pinfunction "NC_110") (pintype "passive"))
    )
    (net (code "141") (name "unconnected-(U101B-NC-Pad111)") (class "Default")
      (node (ref "U101") (pin "111") (pinfunction "NC_111") (pintype "passive"))
    )
    (net (code "142") (name "unconnected-(U101B-NC-Pad112)") (class "Default")
      (node (ref "U101") (pin "112") (pinfunction "NC_112") (pintype "passive"))
    )
    (net (code "143") (name "unconnected-(U101B-NC-Pad113)") (class "Default")
      (node (ref "U101") (pin "113") (pinfunction "NC_113") (pintype "passive"))
    )
    (net (code "144") (name "unconnected-(U101B-NC-Pad114)") (class "Default")
      (node (ref "U101") (pin "114") (pinfunction "NC_114") (pintype "passive"))
    )
    (net (code "145") (name "unconnected-(U101B-NC-Pad115)") (class "Default")
      (node (ref "U101") (pin "115") (pinfunction "NC_115") (pintype "passive"))
    )
    (net (code "146") (name "unconnected-(U101B-NC-Pad116)") (class "Default")
      (node (ref "U101") (pin "116") (pinfunction "NC_116") (pintype "passive"))
    )
    (net (code "147") (name "unconnected-(U101B-NC-Pad117)") (class "Default")
      (node (ref "U101") (pin "117") (pinfunction "NC_117") (pintype "passive"))
    )
    (net (code "148") (name "unconnected-(U101B-NC-Pad118)") (class "Default")
      (node (ref "U101") (pin "118") (pinfunction "NC_118") (pintype "passive"))
    )
    (net (code "149") (name "unconnected-(U101B-NC-Pad119)") (class "Default")
      (node (ref "U101") (pin "119") (pinfunction "NC_119") (pintype "passive"))
    )
    (net (code "150") (name "unconnected-(U101B-NC-Pad120)") (class "Default")
      (node (ref "U101") (pin "120") (pinfunction "NC_120") (pintype "passive"))
    )
    (net (code "151") (name "unconnected-(U101B-NC-Pad121)") (class "Default")
      (node (ref "U101") (pin "121") (pinfunction "NC_121") (pintype "passive"))
    )
    (net (code "152") (name "unconnected-(U101B-NC-Pad122)") (class "Default")
      (node (ref "U101") (pin "122") (pinfunction "NC_122") (pintype "passive"))
    )
    (net (code "153") (name "unconnected-(U101B-NC-Pad123)") (class "Default")
      (node (ref "U101") (pin "123") (pinfunction "NC_123") (pintype "passive"))
    )
    (net (code "154") (name "unconnected-(U101B-NC-Pad124)") (class "Default")
      (node (ref "U101") (pin "124") (pinfunction "NC_124") (pintype "passive"))
    )
    (net (code "155") (name "unconnected-(U101B-NC-Pad125)") (class "Default")
      (node (ref "U101") (pin "125") (pinfunction "NC_125") (pintype "passive"))
    )
    (net (code "156") (name "unconnected-(U101B-NC-Pad126)") (class "Default")
      (node (ref "U101") (pin "126") (pinfunction "NC_126") (pintype "passive"))
    )
    (net (code "157") (name "unconnected-(U101B-NC-Pad127)") (class "Default")
      (node (ref "U101") (pin "127") (pinfunction "NC_127") (pintype "passive"))
    )
    (net (code "158") (name "unconnected-(U102-NC-Pad4)") (class "Default")
      (node (ref "U102") (pin "4") (pinfunction "NC_4") (pintype "passive"))
    )
  )
)
